# 4Z.net
KiCad netlist of a schematic drawn in Altium Designer
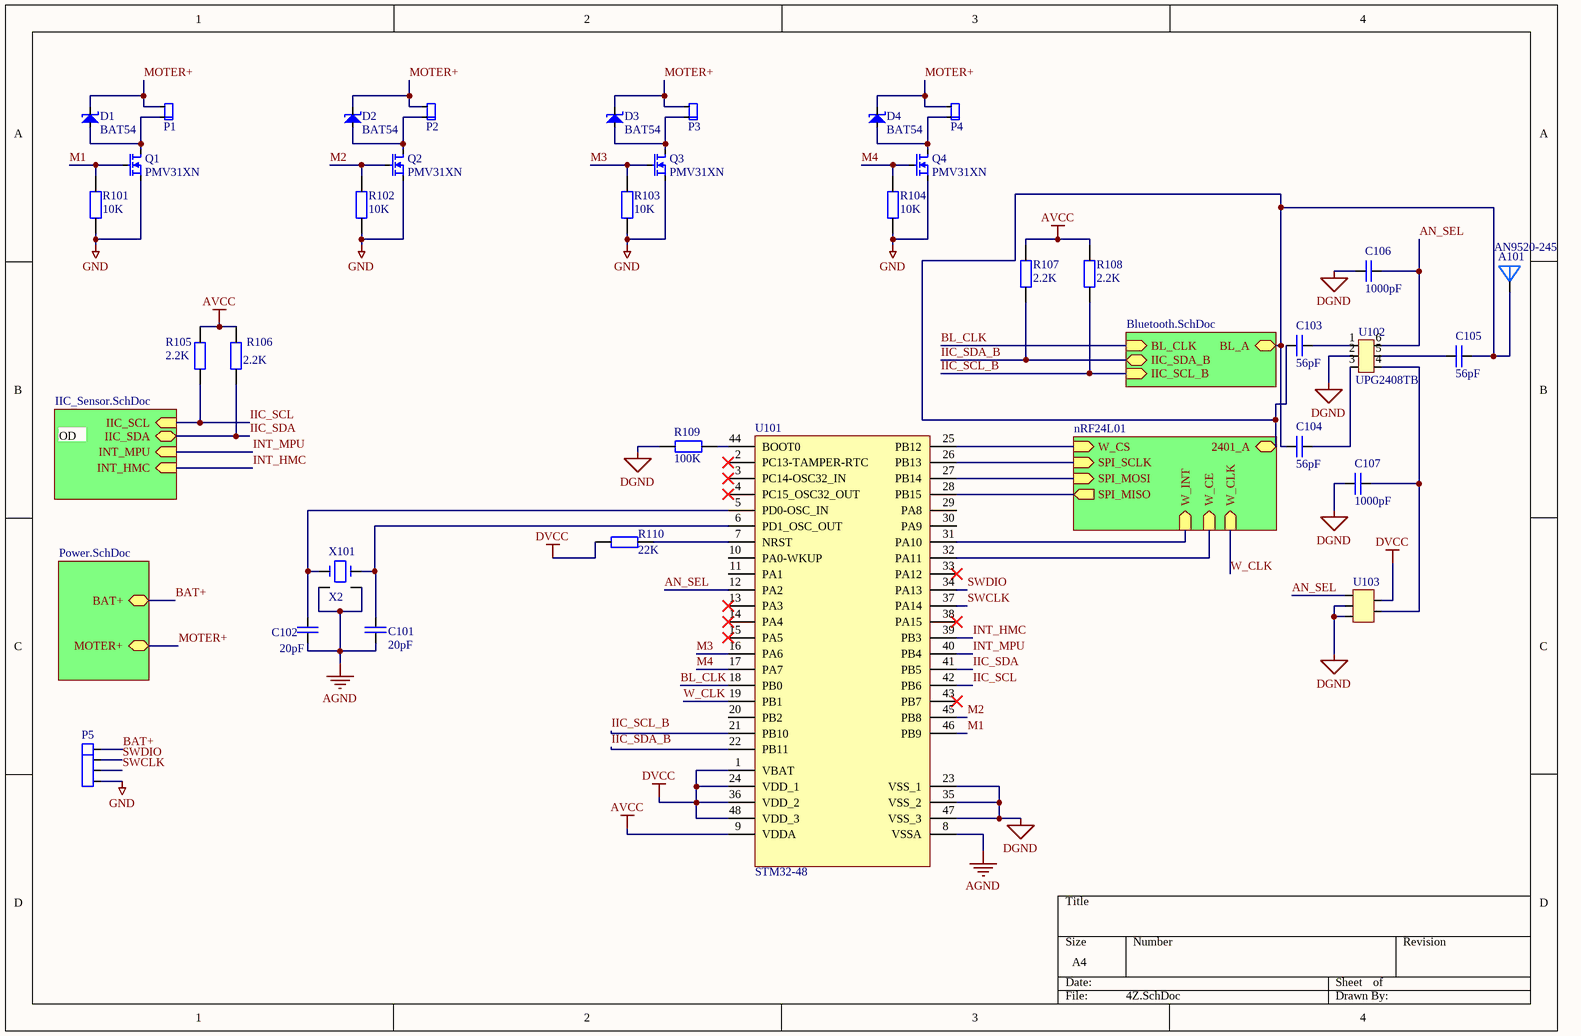
[diagram p0: 4Z.SchDoc]

(export (version "E")
  (design (tool "Eeschema 10.0.6"))
  (components
    (comp (ref "A101")
      (value "AN9520-245")
      (footprint "AN9520-245")
      (description "antenna")
      (libsource (lib "Library") (part "AN9520-245"))
    )
    (comp (ref "C101") (value "20pF") (footprint "0603") (libsource (lib "Library") (part "C0603")))
    (comp (ref "C102") (value "20pF") (footprint "0603") (libsource (lib "Library") (part "C0603")))
    (comp (ref "C103") (value "56pF") (footprint "0603") (libsource (lib "Library") (part "C0603")))
    (comp (ref "C104") (value "56pF") (footprint "0603") (libsource (lib "Library") (part "C0603")))
    (comp (ref "C105") (value "56pF") (footprint "0603") (libsource (lib "Library") (part "C0603")))
    (comp (ref "C106") (value "1000pF") (footprint "0603") (libsource (lib "Library") (part "C0603")))
    (comp (ref "C107") (value "1000pF") (footprint "0603") (libsource (lib "Library") (part "C0603")))
    (comp (ref "D1") (value "BAT54") (footprint "BAT54") (libsource (lib "Library") (part "BAT54")))
    (comp (ref "D2") (value "BAT54") (footprint "BAT54") (libsource (lib "Library") (part "BAT54")))
    (comp (ref "D3") (value "BAT54") (footprint "BAT54") (libsource (lib "Library") (part "BAT54")))
    (comp (ref "D4") (value "BAT54") (footprint "BAT54") (libsource (lib "Library") (part "BAT54")))
    (comp (ref "P1") (value "DIP_2") (footprint "PAD_M") (libsource (lib "Library") (part "DIP_2")))
    (comp (ref "P2") (value "DIP_2") (footprint "PAD_M") (libsource (lib "Library") (part "DIP_2")))
    (comp (ref "P3") (value "DIP_2") (footprint "PAD_M") (libsource (lib "Library") (part "DIP_2")))
    (comp (ref "P4") (value "DIP_2") (footprint "PAD_M") (libsource (lib "Library") (part "DIP_2")))
    (comp (ref "P5") (value "DIP_4") (footprint "DIP_4") (libsource (lib "Library") (part "DIP_4")))
    (comp (ref "Q1") (value "PMV31XN") (footprint "PMV31XN") (libsource (lib "Library") (part "PMV31XN")))
    (comp (ref "Q2") (value "PMV31XN") (footprint "PMV31XN") (libsource (lib "Library") (part "PMV31XN")))
    (comp (ref "Q3") (value "PMV31XN") (footprint "PMV31XN") (libsource (lib "Library") (part "PMV31XN")))
    (comp (ref "Q4") (value "PMV31XN") (footprint "PMV31XN") (libsource (lib "Library") (part "PMV31XN")))
    (comp (ref "R101") (value "10K") (footprint "0603") (libsource (lib "Library") (part "R0603")))
    (comp (ref "R102") (value "10K") (footprint "0603") (libsource (lib "Library") (part "R0603")))
    (comp (ref "R103") (value "10K") (footprint "0603") (libsource (lib "Library") (part "R0603")))
    (comp (ref "R104") (value "10K") (footprint "0603") (libsource (lib "Library") (part "R0603")))
    (comp (ref "R105") (value "2.2K") (footprint "0603") (libsource (lib "Library") (part "R0603")))
    (comp (ref "R106") (value "2.2K") (footprint "0603") (libsource (lib "Library") (part "R0603")))
    (comp (ref "R107") (value "2.2K") (footprint "0603") (libsource (lib "Library") (part "R0603")))
    (comp (ref "R108") (value "2.2K") (footprint "0603") (libsource (lib "Library") (part "R0603")))
    (comp (ref "R109") (value "100K") (footprint "0603") (libsource (lib "Library") (part "R0603")))
    (comp (ref "R110") (value "22K") (footprint "0603") (libsource (lib "Library") (part "R0603")))
    (comp (ref "U101")
      (value "STM32-48")
      (footprint "STM32-48")
      (libsource (lib "Library") (part "STM32-48"))
    )
    (comp (ref "U102")
      (value "UPG2408TB")
      (footprint "UPF2408TB")
      (libsource (lib "Library") (part "UPG2408TB"))
    )
    (comp (ref "U103")
      (value "SN74LVC1G02DBVR")
      (footprint "SN74LVC1G02DBVR")
      (libsource (lib "Library") (part "SN74LVC1G02DBVR"))
    )
    (comp (ref "X101")
      (value "X2")
      (footprint "3225")
      (description "3225")
      (libsource (lib "Library") (part "X2"))
    )
  )
  (nets
    (net (code "1") (name "/2401_A") (class "Default")
      (node (ref "A101") (pin "1") (pinfunction "1_1") (pintype "passive"))
      (node (ref "C103") (pin "1") (pinfunction "1_1") (pintype "passive"))
      (node (ref "C104") (pin "1") (pinfunction "1_1") (pintype "passive"))
      (node (ref "C105") (pin "2") (pinfunction "2_2") (pintype "passive"))
    )
    (net (code "2") (name "/AN_SEL") (class "Default")
      (node (ref "C106") (pin "1") (pinfunction "1_1") (pintype "passive"))
      (node (ref "U101") (pin "12") (pinfunction "PA2_12") (pintype "passive"))
      (node (ref "U102") (pin "6") (pinfunction "V1_6") (pintype "passive"))
      (node (ref "U103") (pin "1") (pinfunction "IN_1") (pintype "passive"))
    )
    (net (code "3") (name "/BAT+") (class "Default")
      (node (ref "P5") (pin "1") (pinfunction "1_1") (pintype "passive"))
    )
    (net (code "4") (name "/BL_CLK") (class "Default")
      (node (ref "U101") (pin "18") (pinfunction "PB0_18") (pintype "passive"))
    )
    (net (code "5") (name "/IIC_SCL") (class "Default")
      (node (ref "R105") (pin "2") (pinfunction "2_2") (pintype "passive"))
      (node (ref "U101") (pin "42") (pinfunction "PB6_42") (pintype "passive"))
    )
    (net (code "6") (name "/IIC_SCL_B") (class "Default")
      (node (ref "R108") (pin "2") (pinfunction "2_2") (pintype "passive"))
      (node (ref "U101") (pin "21") (pinfunction "PB10_21") (pintype "passive"))
    )
    (net (code "7") (name "/IIC_SDA") (class "Default")
      (node (ref "R106") (pin "2") (pinfunction "2_2") (pintype "passive"))
      (node (ref "U101") (pin "41") (pinfunction "PB5_41") (pintype "passive"))
    )
    (net (code "8") (name "/IIC_SDA_B") (class "Default")
      (node (ref "R107") (pin "2") (pinfunction "2_2") (pintype "passive"))
      (node (ref "U101") (pin "22") (pinfunction "PB11_22") (pintype "passive"))
    )
    (net (code "9") (name "/INT_HMC") (class "Default")
      (node (ref "U101") (pin "39") (pinfunction "PB3_39") (pintype "passive"))
    )
    (net (code "10") (name "/INT_MPU") (class "Default")
      (node (ref "U101") (pin "40") (pinfunction "PB4_40") (pintype "passive"))
    )
    (net (code "11") (name "/M1") (class "Default")
      (node (ref "Q1") (pin "1") (pinfunction "1_1") (pintype "passive"))
      (node (ref "R101") (pin "1") (pinfunction "1_1") (pintype "passive"))
      (node (ref "U101") (pin "46") (pinfunction "PB9_46") (pintype "passive"))
    )
    (net (code "12") (name "/M2") (class "Default")
      (node (ref "Q2") (pin "1") (pinfunction "1_1") (pintype "passive"))
      (node (ref "R102") (pin "1") (pinfunction "1_1") (pintype "passive"))
      (node (ref "U101") (pin "45") (pinfunction "PB8_45") (pintype "passive"))
    )
    (net (code "13") (name "/M3") (class "Default")
      (node (ref "Q3") (pin "1") (pinfunction "1_1") (pintype "passive"))
      (node (ref "R103") (pin "1") (pinfunction "1_1") (pintype "passive"))
      (node (ref "U101") (pin "16") (pinfunction "PA6_16") (pintype "passive"))
    )
    (net (code "14") (name "/M4") (class "Default")
      (node (ref "Q4") (pin "1") (pinfunction "1_1") (pintype "passive"))
      (node (ref "R104") (pin "1") (pinfunction "1_1") (pintype "passive"))
      (node (ref "U101") (pin "17") (pinfunction "PA7_17") (pintype "passive"))
    )
    (net (code "15") (name "/MOTER+") (class "Default")
      (node (ref "D1") (pin "3") (pinfunction "3_3") (pintype "passive"))
      (node (ref "D2") (pin "3") (pinfunction "3_3") (pintype "passive"))
      (node (ref "D3") (pin "3") (pinfunction "3_3") (pintype "passive"))
      (node (ref "D4") (pin "3") (pinfunction "3_3") (pintype "passive"))
      (node (ref "P1") (pin "2") (pinfunction "2_2") (pintype "passive"))
      (node (ref "P2") (pin "2") (pinfunction "2_2") (pintype "passive"))
      (node (ref "P3") (pin "2") (pinfunction "2_2") (pintype "passive"))
      (node (ref "P4") (pin "2") (pinfunction "2_2") (pintype "passive"))
    )
    (net (code "16") (name "/SPI_MISO") (class "Default")
      (node (ref "U101") (pin "28") (pinfunction "PB15_28") (pintype "passive"))
    )
    (net (code "17") (name "/SPI_MOSI") (class "Default")
      (node (ref "U101") (pin "27") (pinfunction "PB14_27") (pintype "passive"))
    )
    (net (code "18") (name "/SPI_SCLK") (class "Default")
      (node (ref "U101") (pin "26") (pinfunction "PB13_26") (pintype "passive"))
    )
    (net (code "19") (name "/SWCLK") (class "Default")
      (node (ref "P5") (pin "3") (pinfunction "3_3") (pintype "passive"))
      (node (ref "U101") (pin "37") (pinfunction "PA14_37") (pintype "passive"))
    )
    (net (code "20") (name "/SWDIO") (class "Default")
      (node (ref "P5") (pin "2") (pinfunction "2_2") (pintype "passive"))
      (node (ref "U101") (pin "34") (pinfunction "PA13_34") (pintype "passive"))
    )
    (net (code "21") (name "/W_CE") (class "Default")
      (node (ref "U101") (pin "32") (pinfunction "PA11_32") (pintype "passive"))
    )
    (net (code "22") (name "/W_CLK") (class "Default")
      (node (ref "U101") (pin "19") (pinfunction "PB1_19") (pintype "passive"))
    )
    (net (code "24") (name "/W_CS") (class "Default")
      (node (ref "U101") (pin "25") (pinfunction "PB12_25") (pintype "passive"))
    )
    (net (code "25") (name "/W_INT") (class "Default")
      (node (ref "U101") (pin "31") (pinfunction "PA10_31") (pintype "passive"))
    )
    (net (code "26") (name "AGND") (class "Default")
      (node (ref "C101") (pin "1") (pinfunction "1_1") (pintype "passive"))
      (node (ref "C102") (pin "1") (pinfunction "1_1") (pintype "passive"))
      (node (ref "U101") (pin "8") (pinfunction "VSSA_8") (pintype "passive"))
      (node (ref "X101") (pin "2") (pinfunction "2_2") (pintype "passive"))
      (node (ref "X101") (pin "4") (pinfunction "4_4") (pintype "passive"))
    )
    (net (code "27") (name "AVCC") (class "Default")
      (node (ref "R105") (pin "1") (pinfunction "1_1") (pintype "passive"))
      (node (ref "R106") (pin "1") (pinfunction "1_1") (pintype "passive"))
      (node (ref "R107") (pin "1") (pinfunction "1_1") (pintype "passive"))
      (node (ref "R108") (pin "1") (pinfunction "1_1") (pintype "passive"))
      (node (ref "U101") (pin "9") (pinfunction "VDDA_9") (pintype "passive"))
    )
    (net (code "28") (name "DGND") (class "Default")
      (node (ref "C106") (pin "2") (pinfunction "2_2") (pintype "passive"))
      (node (ref "C107") (pin "2") (pinfunction "2_2") (pintype "passive"))
      (node (ref "R109") (pin "2") (pinfunction "2_2") (pintype "passive"))
      (node (ref "U101") (pin "23") (pinfunction "VSS_1_23") (pintype "passive"))
      (node (ref "U101") (pin "35") (pinfunction "VSS_2_35") (pintype "passive"))
      (node (ref "U101") (pin "47") (pinfunction "VSS_3_47") (pintype "passive"))
      (node (ref "U102") (pin "2") (pinfunction "GND_2") (pintype "passive"))
      (node (ref "U103") (pin "2") (pinfunction "IN_2") (pintype "passive"))
      (node (ref "U103") (pin "3") (pinfunction "GND_3") (pintype "passive"))
    )
    (net (code "29") (name "DVCC") (class "Default")
      (node (ref "R110") (pin "2") (pinfunction "2_2") (pintype "passive"))
      (node (ref "U101") (pin "1") (pinfunction "VBAT_1") (pintype "passive"))
      (node (ref "U101") (pin "24") (pinfunction "VDD_1_24") (pintype "passive"))
      (node (ref "U101") (pin "36") (pinfunction "VDD_2_36") (pintype "passive"))
      (node (ref "U101") (pin "48") (pinfunction "VDD_3_48") (pintype "passive"))
      (node (ref "U103") (pin "4") (pinfunction "VCC_4") (pintype "passive"))
    )
    (net (code "30") (name "GND") (class "Default")
      (node (ref "P5") (pin "4") (pinfunction "4_4") (pintype "passive"))
      (node (ref "Q1") (pin "2") (pinfunction "2_2") (pintype "passive"))
      (node (ref "Q2") (pin "2") (pinfunction "2_2") (pintype "passive"))
      (node (ref "Q3") (pin "2") (pinfunction "2_2") (pintype "passive"))
      (node (ref "Q4") (pin "2") (pinfunction "2_2") (pintype "passive"))
      (node (ref "R101") (pin "2") (pinfunction "2_2") (pintype "passive"))
      (node (ref "R102") (pin "2") (pinfunction "2_2") (pintype "passive"))
      (node (ref "R103") (pin "2") (pinfunction "2_2") (pintype "passive"))
      (node (ref "R104") (pin "2") (pinfunction "2_2") (pintype "passive"))
    )
    (net (code "31") (name "Net-(D1-Pad1)") (class "Default")
      (node (ref "D1") (pin "1") (pinfunction "1_1") (pintype "passive"))
      (node (ref "P1") (pin "1") (pinfunction "1_1") (pintype "passive"))
      (node (ref "Q1") (pin "3") (pinfunction "3_3") (pintype "passive"))
    )
    (net (code "32") (name "Net-(D2-Pad1)") (class "Default")
      (node (ref "D2") (pin "1") (pinfunction "1_1") (pintype "passive"))
      (node (ref "P2") (pin "1") (pinfunction "1_1") (pintype "passive"))
      (node (ref "Q2") (pin "3") (pinfunction "3_3") (pintype "passive"))
    )
    (net (code "33") (name "Net-(D3-Pad1)") (class "Default")
      (node (ref "D3") (pin "1") (pinfunction "1_1") (pintype "passive"))
      (node (ref "P3") (pin "1") (pinfunction "1_1") (pintype "passive"))
      (node (ref "Q3") (pin "3") (pinfunction "3_3") (pintype "passive"))
    )
    (net (code "34") (name "Net-(D4-Pad1)") (class "Default")
      (node (ref "D4") (pin "1") (pinfunction "1_1") (pintype "passive"))
      (node (ref "P4") (pin "1") (pinfunction "1_1") (pintype "passive"))
      (node (ref "Q4") (pin "3") (pinfunction "3_3") (pintype "passive"))
    )
    (net (code "35") (name "Net-(U101-BOOT0)") (class "Default")
      (node (ref "R109") (pin "1") (pinfunction "1_1") (pintype "passive"))
      (node (ref "U101") (pin "44") (pinfunction "BOOT0_44") (pintype "passive"))
    )
    (net (code "36") (name "Net-(U101-NRST)") (class "Default")
      (node (ref "R110") (pin "1") (pinfunction "1_1") (pintype "passive"))
      (node (ref "U101") (pin "7") (pinfunction "NRST_7") (pintype "passive"))
    )
    (net (code "37") (name "Net-(U101-PD0-OSC_IN)") (class "Default")
      (node (ref "C102") (pin "2") (pinfunction "2_2") (pintype "passive"))
      (node (ref "U101") (pin "5") (pinfunction "PD0-OSC_IN_5") (pintype "passive"))
      (node (ref "X101") (pin "3") (pintype "passive"))
    )
    (net (code "38") (name "Net-(U101-PD1_OSC_OUT)") (class "Default")
      (node (ref "C101") (pin "2") (pinfunction "2_2") (pintype "passive"))
      (node (ref "U101") (pin "6") (pinfunction "PD1_OSC_OUT_6") (pintype "passive"))
      (node (ref "X101") (pin "1") (pintype "passive"))
    )
    (net (code "39") (name "Net-(U102-RF1)") (class "Default")
      (node (ref "C103") (pin "2") (pinfunction "2_2") (pintype "passive"))
      (node (ref "U102") (pin "1") (pinfunction "RF1_1") (pintype "passive"))
    )
    (net (code "40") (name "Net-(U102-RF2)") (class "Default")
      (node (ref "C104") (pin "2") (pinfunction "2_2") (pintype "passive"))
      (node (ref "U102") (pin "3") (pinfunction "RF2_3") (pintype "passive"))
    )
    (net (code "41") (name "Net-(U102-RFC)") (class "Default")
      (node (ref "C105") (pin "1") (pinfunction "1_1") (pintype "passive"))
      (node (ref "U102") (pin "5") (pinfunction "RFC_5") (pintype "passive"))
    )
    (net (code "42") (name "Net-(U102-V2)") (class "Default")
      (node (ref "C107") (pin "1") (pinfunction "1_1") (pintype "passive"))
      (node (ref "U102") (pin "4") (pinfunction "V2_4") (pintype "passive"))
      (node (ref "U103") (pin "5") (pinfunction "OUT_5") (pintype "passive"))
    )
    (net (code "43") (name "unconnected-(U101-PA0-WKUP-Pad10)") (class "Default")
      (node (ref "U101") (pin "10") (pinfunction "PA0-WKUP_10") (pintype "passive"))
    )
    (net (code "44") (name "unconnected-(U101-PA1-Pad11)") (class "Default")
      (node (ref "U101") (pin "11") (pinfunction "PA1_11") (pintype "passive"))
    )
    (net (code "45") (name "unconnected-(U101-PA3-Pad13)") (class "Default")
      (node (ref "U101") (pin "13") (pinfunction "PA3_13") (pintype "passive+no_connect"))
    )
    (net (code "46") (name "unconnected-(U101-PA4-Pad14)") (class "Default")
      (node (ref "U101") (pin "14") (pinfunction "PA4_14") (pintype "passive+no_connect"))
    )
    (net (code "47") (name "unconnected-(U101-PA5-Pad15)") (class "Default")
      (node (ref "U101") (pin "15") (pinfunction "PA5_15") (pintype "passive+no_connect"))
    )
    (net (code "48") (name "unconnected-(U101-PA8-Pad29)") (class "Default")
      (node (ref "U101") (pin "29") (pinfunction "PA8_29") (pintype "passive"))
    )
    (net (code "49") (name "unconnected-(U101-PA9-Pad30)") (class "Default")
      (node (ref "U101") (pin "30") (pinfunction "PA9_30") (pintype "passive"))
    )
    (net (code "50") (name "unconnected-(U101-PA12-Pad33)") (class "Default")
      (node (ref "U101") (pin "33") (pinfunction "PA12_33") (pintype "passive+no_connect"))
    )
    (net (code "51") (name "unconnected-(U101-PA15-Pad38)") (class "Default")
      (node (ref "U101") (pin "38") (pinfunction "PA15_38") (pintype "passive+no_connect"))
    )
    (net (code "52") (name "unconnected-(U101-PB2-Pad20)") (class "Default")
      (node (ref "U101") (pin "20") (pinfunction "PB2_20") (pintype "passive"))
    )
    (net (code "53") (name "unconnected-(U101-PB7-Pad43)") (class "Default")
      (node (ref "U101") (pin "43") (pinfunction "PB7_43") (pintype "passive+no_connect"))
    )
    (net (code "54") (name "unconnected-(U101-PC13-TAMPER-RTC-Pad2)") (class "Default")
      (node (ref "U101") (pin "2") (pinfunction "PC13-TAMPER-RTC_2") (pintype "passive+no_connect"))
    )
    (net (code "55") (name "unconnected-(U101-PC14-OSC32_IN-Pad3)") (class "Default")
      (node (ref "U101") (pin "3") (pinfunction "PC14-OSC32_IN_3") (pintype "passive+no_connect"))
    )
    (net (code "56") (name "unconnected-(U101-PC15_OSC32_OUT-Pad4)") (class "Default")
      (node (ref "U101") (pin "4") (pinfunction "PC15_OSC32_OUT_4") (pintype "passive+no_connect"))
    )
  )
)
